# u10-small.net
KiCad netlist of a schematic drawn in EAGLE
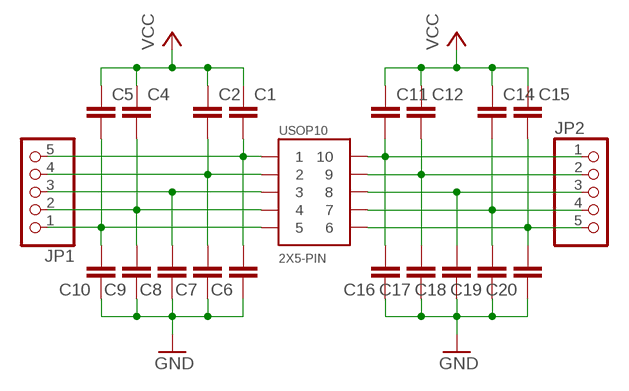
[diagram p0: schematic, sheet 1]

(export (version "E")
  (design (tool "Eeschema 10.0.6"))
  (components
    (comp (ref "C1")
      (value "C-EUC0603")
      (footprint "eagle-import:C0603")
      (libsource (lib "eagle-import") (part "C-EUC0603"))
    )
    (comp (ref "C2")
      (value "C-EUC0603")
      (footprint "eagle-import:C0603")
      (libsource (lib "eagle-import") (part "C-EUC0603"))
    )
    (comp (ref "C4")
      (value "C-EUC0603")
      (footprint "eagle-import:C0603")
      (libsource (lib "eagle-import") (part "C-EUC0603"))
    )
    (comp (ref "C5")
      (value "C-EUC0603")
      (footprint "eagle-import:C0603")
      (libsource (lib "eagle-import") (part "C-EUC0603"))
    )
    (comp (ref "C6")
      (value "C-EUC0805")
      (footprint "eagle-import:C0805")
      (libsource (lib "eagle-import") (part "C-EUC0805"))
    )
    (comp (ref "C7")
      (value "C-EUC0805")
      (footprint "eagle-import:C0805")
      (libsource (lib "eagle-import") (part "C-EUC0805"))
    )
    (comp (ref "C8")
      (value "C-EUC0805")
      (footprint "eagle-import:C0805")
      (libsource (lib "eagle-import") (part "C-EUC0805"))
    )
    (comp (ref "C9")
      (value "C-EUC0805")
      (footprint "eagle-import:C0805")
      (libsource (lib "eagle-import") (part "C-EUC0805"))
    )
    (comp (ref "C10")
      (value "C-EUC0805")
      (footprint "eagle-import:C0805")
      (libsource (lib "eagle-import") (part "C-EUC0805"))
    )
    (comp (ref "C11")
      (value "C-EUC0603")
      (footprint "eagle-import:C0603")
      (libsource (lib "eagle-import") (part "C-EUC0603"))
    )
    (comp (ref "C12")
      (value "C-EUC0603")
      (footprint "eagle-import:C0603")
      (libsource (lib "eagle-import") (part "C-EUC0603"))
    )
    (comp (ref "C14")
      (value "C-EUC0603")
      (footprint "eagle-import:C0603")
      (libsource (lib "eagle-import") (part "C-EUC0603"))
    )
    (comp (ref "C15")
      (value "C-EUC0603")
      (footprint "eagle-import:C0603")
      (libsource (lib "eagle-import") (part "C-EUC0603"))
    )
    (comp (ref "C16")
      (value "C-EUC0805")
      (footprint "eagle-import:C0805")
      (libsource (lib "eagle-import") (part "C-EUC0805"))
    )
    (comp (ref "C17")
      (value "C-EUC0805")
      (footprint "eagle-import:C0805")
      (libsource (lib "eagle-import") (part "C-EUC0805"))
    )
    (comp (ref "C18")
      (value "C-EUC0805")
      (footprint "eagle-import:C0805")
      (libsource (lib "eagle-import") (part "C-EUC0805"))
    )
    (comp (ref "C19")
      (value "C-EUC0805")
      (footprint "eagle-import:C0805")
      (libsource (lib "eagle-import") (part "C-EUC0805"))
    )
    (comp (ref "C20")
      (value "C-EUC0805")
      (footprint "eagle-import:C0805")
      (libsource (lib "eagle-import") (part "C-EUC0805"))
    )
    (comp (ref "JP1")
      (value "PINHD-1X5")
      (footprint "eagle-import:1X05")
      (libsource (lib "eagle-import") (part "PINHD-1X5"))
    )
    (comp (ref "JP2")
      (value "PINHD-1X5")
      (footprint "eagle-import:1X05")
      (libsource (lib "eagle-import") (part "PINHD-1X5"))
    )
    (comp (ref "USOP10")
      (value "2X5-PIN")
      (footprint "eagle-import:USOP10")
      (libsource (lib "eagle-import") (part "2X5-PIN"))
    )
  )
  (nets
    (net (code "1") (name "GND") (class "Default")
      (node (ref "C10") (pin "1") (pinfunction "1_1") (pintype "passive"))
      (node (ref "C16") (pin "1") (pinfunction "1_1") (pintype "passive"))
      (node (ref "C17") (pin "1") (pinfunction "1_1") (pintype "passive"))
      (node (ref "C18") (pin "1") (pinfunction "1_1") (pintype "passive"))
      (node (ref "C19") (pin "1") (pinfunction "1_1") (pintype "passive"))
      (node (ref "C20") (pin "1") (pinfunction "1_1") (pintype "passive"))
      (node (ref "C6") (pin "1") (pinfunction "1_1") (pintype "passive"))
      (node (ref "C7") (pin "1") (pinfunction "1_1") (pintype "passive"))
      (node (ref "C8") (pin "1") (pinfunction "1_1") (pintype "passive"))
      (node (ref "C9") (pin "1") (pinfunction "1_1") (pintype "passive"))
    )
    (net (code "2") (name "Net-(USOP10-1)") (class "Default")
      (node (ref "C1") (pin "2") (pinfunction "2_2") (pintype "passive"))
      (node (ref "C6") (pin "2") (pinfunction "2_2") (pintype "passive"))
      (node (ref "JP1") (pin "5") (pinfunction "5_5") (pintype "passive"))
      (node (ref "USOP10") (pin "P$1") (pinfunction "1_P$1") (pintype "bidirectional"))
    )
    (net (code "3") (name "Net-(USOP10-2)") (class "Default")
      (node (ref "C2") (pin "2") (pinfunction "2_2") (pintype "passive"))
      (node (ref "C7") (pin "2") (pinfunction "2_2") (pintype "passive"))
      (node (ref "JP1") (pin "4") (pinfunction "4_4") (pintype "passive"))
      (node (ref "USOP10") (pin "P$2") (pinfunction "2_P$2") (pintype "bidirectional"))
    )
    (net (code "4") (name "Net-(USOP10-3)") (class "Default")
      (node (ref "C8") (pin "2") (pinfunction "2_2") (pintype "passive"))
      (node (ref "JP1") (pin "3") (pinfunction "3_3") (pintype "passive"))
      (node (ref "USOP10") (pin "P$3") (pinfunction "3_P$3") (pintype "bidirectional"))
    )
    (net (code "5") (name "Net-(USOP10-4)") (class "Default")
      (node (ref "C4") (pin "2") (pinfunction "2_2") (pintype "passive"))
      (node (ref "C9") (pin "2") (pinfunction "2_2") (pintype "passive"))
      (node (ref "JP1") (pin "2") (pinfunction "2_2") (pintype "passive"))
      (node (ref "USOP10") (pin "P$4") (pinfunction "4_P$4") (pintype "bidirectional"))
    )
    (net (code "6") (name "Net-(USOP10-5)") (class "Default")
      (node (ref "C10") (pin "2") (pinfunction "2_2") (pintype "passive"))
      (node (ref "C5") (pin "2") (pinfunction "2_2") (pintype "passive"))
      (node (ref "JP1") (pin "1") (pinfunction "1_1") (pintype "passive"))
      (node (ref "USOP10") (pin "P$5") (pinfunction "5_P$5") (pintype "bidirectional"))
    )
    (net (code "7") (name "Net-(USOP10-6)") (class "Default")
      (node (ref "C15") (pin "2") (pinfunction "2_2") (pintype "passive"))
      (node (ref "C20") (pin "2") (pinfunction "2_2") (pintype "passive"))
      (node (ref "JP2") (pin "5") (pinfunction "5_5") (pintype "passive"))
      (node (ref "USOP10") (pin "P$6") (pinfunction "6_P$6") (pintype "bidirectional"))
    )
    (net (code "8") (name "Net-(USOP10-7)") (class "Default")
      (node (ref "C14") (pin "2") (pinfunction "2_2") (pintype "passive"))
      (node (ref "C19") (pin "2") (pinfunction "2_2") (pintype "passive"))
      (node (ref "JP2") (pin "4") (pinfunction "4_4") (pintype "passive"))
      (node (ref "USOP10") (pin "P$7") (pinfunction "7_P$7") (pintype "bidirectional"))
    )
    (net (code "9") (name "Net-(USOP10-8)") (class "Default")
      (node (ref "C18") (pin "2") (pinfunction "2_2") (pintype "passive"))
      (node (ref "JP2") (pin "3") (pinfunction "3_3") (pintype "passive"))
      (node (ref "USOP10") (pin "P$8") (pinfunction "8_P$8") (pintype "bidirectional"))
    )
    (net (code "10") (name "Net-(USOP10-9)") (class "Default")
      (node (ref "C12") (pin "2") (pinfunction "2_2") (pintype "passive"))
      (node (ref "C17") (pin "2") (pinfunction "2_2") (pintype "passive"))
      (node (ref "JP2") (pin "2") (pinfunction "2_2") (pintype "passive"))
      (node (ref "USOP10") (pin "P$9") (pinfunction "9_P$9") (pintype "bidirectional"))
    )
    (net (code "11") (name "Net-(USOP10-10)") (class "Default")
      (node (ref "C11") (pin "2") (pinfunction "2_2") (pintype "passive"))
      (node (ref "C16") (pin "2") (pinfunction "2_2") (pintype "passive"))
      (node (ref "JP2") (pin "1") (pinfunction "1_1") (pintype "passive"))
      (node (ref "USOP10") (pin "P$10") (pinfunction "10_P$10") (pintype "bidirectional"))
    )
    (net (code "12") (name "VCC") (class "Default")
      (node (ref "C1") (pin "1") (pinfunction "1_1") (pintype "passive"))
      (node (ref "C11") (pin "1") (pinfunction "1_1") (pintype "passive"))
      (node (ref "C12") (pin "1") (pinfunction "1_1") (pintype "passive"))
      (node (ref "C14") (pin "1") (pinfunction "1_1") (pintype "passive"))
      (node (ref "C15") (pin "1") (pinfunction "1_1") (pintype "passive"))
      (node (ref "C2") (pin "1") (pinfunction "1_1") (pintype "passive"))
      (node (ref "C4") (pin "1") (pinfunction "1_1") (pintype "passive"))
      (node (ref "C5") (pin "1") (pinfunction "1_1") (pintype "passive"))
    )
  )
)
